# TC_IC3.net
KiCad netlist of a schematic drawn in Altium Designer
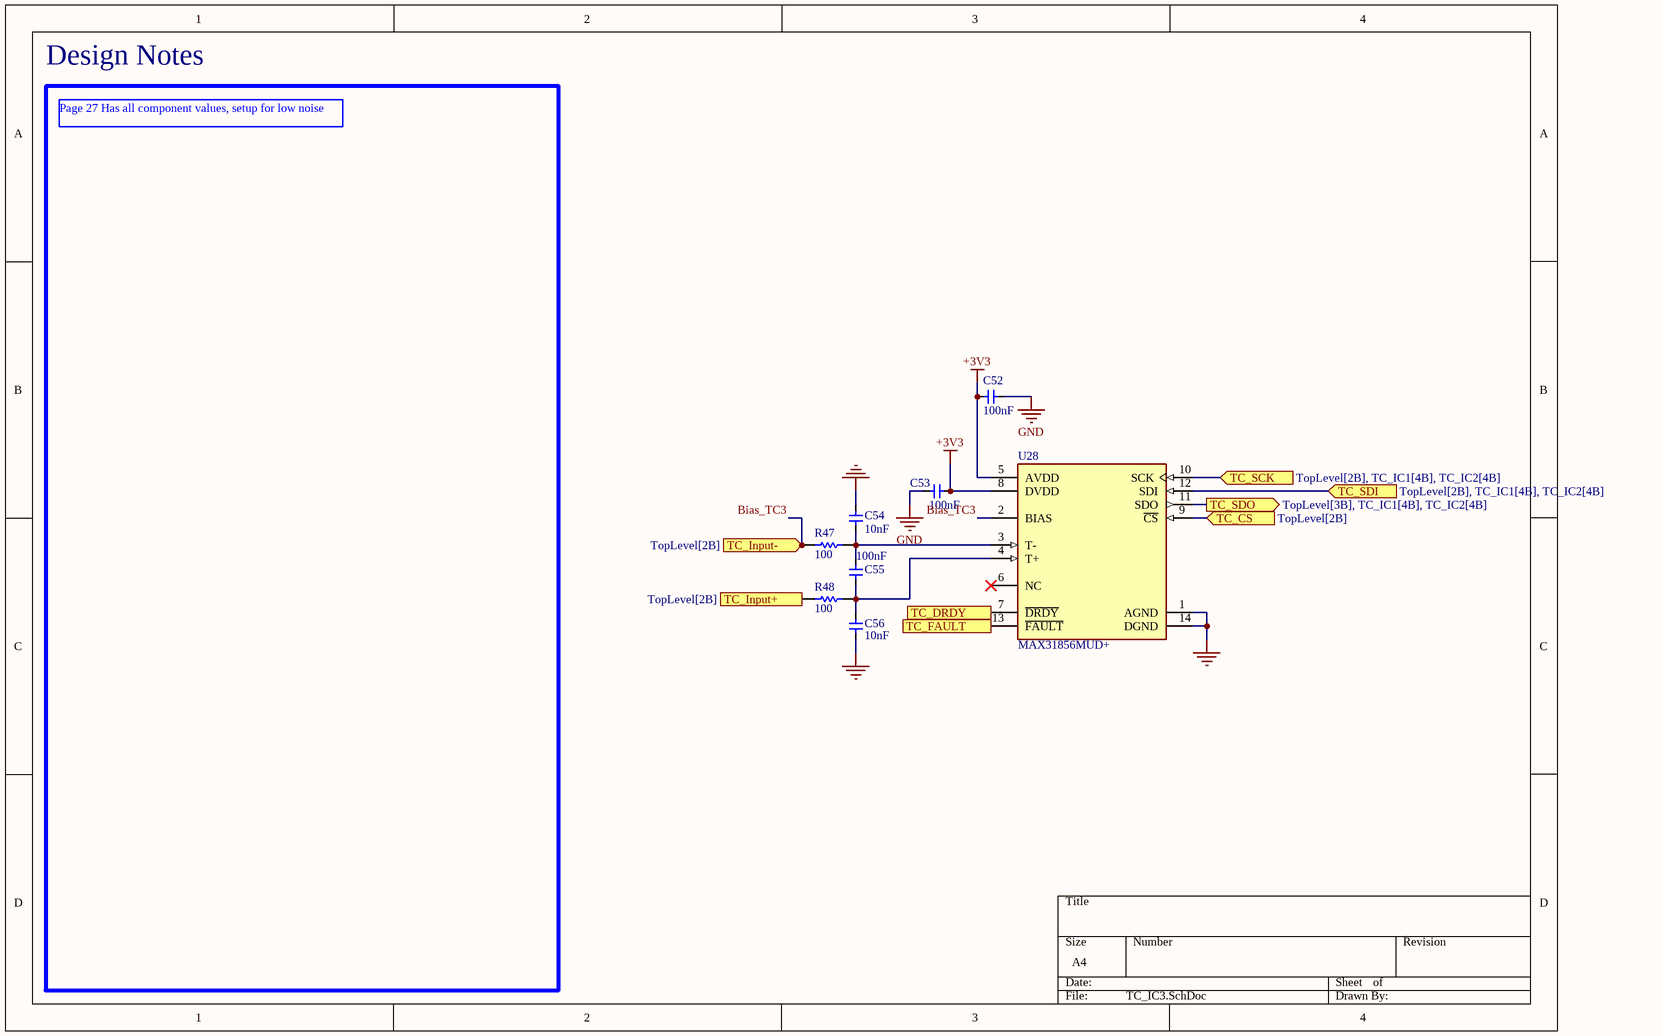
[diagram p0: TC_IC3.SchDoc]

(export (version "E")
  (design (tool "Eeschema 10.0.6"))
  (components
    (comp (ref "C52")
      (value "100nF")
      (footprint "0.1uF-FP-CGA3E-0_3-0_1-IPC_A")
      (description "CGA3E2X7R1E104K080AA CAP CER 0.1UF 25V X7R 0603")
      (fields
        (field (name "TOLERANCE") "10%")
        (field (name "MANUFACTURER") "TDK Corporation")
        (field (name "SOURCE") "PlumBay_SchLib.SchLib")
      )
      (libsource (lib "University of Calgary - SOAR") (part "100nF"))
    )
    (comp (ref "C53")
      (value "100nF")
      (footprint "0.1uF-FP-CGA3E-0_3-0_1-IPC_A")
      (description "CGA3E2X7R1E104K080AA CAP CER 0.1UF 25V X7R 0603")
      (fields
        (field (name "TOLERANCE") "10%")
        (field (name "MANUFACTURER") "TDK Corporation")
        (field (name "SOURCE") "PlumBay_SchLib.SchLib")
      )
      (libsource (lib "University of Calgary - SOAR") (part "100nF"))
    )
    (comp (ref "C54")
      (value "10nF")
      (footprint "10000pF-CAP_1608_TDK")
      (description "CAP CER 10000PF 50V X7R 0603")
      (fields
        (field (name "MANUFACTURER") "TDK Corporation")
        (field (name "TOLERANCE") "10%")
        (field (name "SOURCE") "PlumBay_SchLib.SchLib")
      )
      (libsource (lib "University of Calgary - SOAR") (part "CGA3E2X7R1H103K080AA"))
    )
    (comp (ref "C55")
      (value "100nF")
      (footprint "0.1uF-FP-CGA3E-0_3-0_1-IPC_A")
      (description "CGA3E2X7R1E104K080AA CAP CER 0.1UF 25V X7R 0603")
      (fields
        (field (name "TOLERANCE") "10%")
        (field (name "MANUFACTURER") "TDK Corporation")
        (field (name "SOURCE") "PlumBay_SchLib.SchLib")
      )
      (libsource (lib "University of Calgary - SOAR") (part "100nF"))
    )
    (comp (ref "C56")
      (value "10nF")
      (footprint "10000pF-CAP_1608_TDK")
      (description "CAP CER 10000PF 50V X7R 0603")
      (fields
        (field (name "MANUFACTURER") "TDK Corporation")
        (field (name "TOLERANCE") "10%")
        (field (name "SOURCE") "PlumBay_SchLib.SchLib")
      )
      (libsource (lib "University of Calgary - SOAR") (part "CGA3E2X7R1H103K080AA"))
    )
    (comp (ref "R47")
      (value "100")
      (footprint "RESC1608X55X30LL15T15")
      (fields
        (field (name "POWER") "100mW")
        (field (name "TOLERANCE") "1%")
        (field (name "Comment") "ERJ-3EKF1000V")
      )
      (libsource (lib "University of Calgary - SOAR") (part "RES"))
    )
    (comp (ref "R48")
      (value "100")
      (footprint "RESC1608X55X30LL15T15")
      (fields
        (field (name "POWER") "100mW")
        (field (name "TOLERANCE") "1%")
        (field (name "Comment") "ERJ-3EKF1000V")
      )
      (libsource (lib "University of Calgary - SOAR") (part "RES"))
    )
    (comp (ref "U28")
      (value "MAX31856MUD+")
      (footprint "FP-U14-2-MFG")
      (description "Analog Circuit, 1 Func, PDSO14")
      (libsource (lib "University of Calgary - SOAR") (part "746ee3d58a922cadd982a8de1b076a0"))
    )
  )
  (nets
    (net (code "1") (name "+3V3") (class "Default")
      (node (ref "C52") (pin "1") (pinfunction "1_1") (pintype "passive"))
      (node (ref "C53") (pin "1") (pinfunction "1_1") (pintype "passive"))
      (node (ref "U28") (pin "5") (pinfunction "AVDD_5") (pintype "power_in"))
      (node (ref "U28") (pin "8") (pinfunction "DVDD_8") (pintype "power_in"))
    )
    (net (code "2") (name "/Bias_TC3") (class "Default")
      (node (ref "R47") (pin "2") (pinfunction "2_2") (pintype "passive"))
      (node (ref "U28") (pin "2") (pinfunction "BIAS_2") (pintype "passive"))
    )
    (net (code "3") (name "/TC_CS") (class "Default")
      (node (ref "U28") (pin "9") (pinfunction "~{CS}_9") (pintype "input"))
    )
    (net (code "4") (name "/TC_DRDY") (class "Default")
      (node (ref "U28") (pin "7") (pinfunction "~{DRDY}_7") (pintype "passive"))
    )
    (net (code "5") (name "/TC_FAULT") (class "Default")
      (node (ref "U28") (pin "13") (pinfunction "~{FAULT}_13") (pintype "passive"))
    )
    (net (code "6") (name "/TC_Input+") (class "Default")
      (node (ref "R48") (pin "2") (pinfunction "2_2") (pintype "passive"))
    )
    (net (code "7") (name "/TC_SCK") (class "Default")
      (node (ref "U28") (pin "10") (pinfunction "SCK_10") (pintype "input"))
    )
    (net (code "8") (name "/TC_SDI") (class "Default")
      (node (ref "U28") (pin "12") (pinfunction "SDI_12") (pintype "input"))
    )
    (net (code "9") (name "/TC_SDO") (class "Default")
      (node (ref "U28") (pin "11") (pinfunction "SDO_11") (pintype "output"))
    )
    (net (code "10") (name "GND") (class "Default")
      (node (ref "C52") (pin "2") (pinfunction "2_2") (pintype "passive"))
      (node (ref "C53") (pin "2") (pinfunction "2_2") (pintype "passive"))
      (node (ref "C54") (pin "1") (pinfunction "1_1") (pintype "passive"))
      (node (ref "C56") (pin "1") (pinfunction "1_1") (pintype "passive"))
      (node (ref "U28") (pin "1") (pinfunction "AGND_1") (pintype "power_in"))
      (node (ref "U28") (pin "14") (pinfunction "DGND_14") (pintype "power_in"))
    )
    (net (code "11") (name "Net-(U28-T+)") (class "Default")
      (node (ref "C55") (pin "1") (pinfunction "1_1") (pintype "passive"))
      (node (ref "C56") (pin "2") (pinfunction "2_2") (pintype "passive"))
      (node (ref "R48") (pin "1") (pinfunction "1_1") (pintype "passive"))
      (node (ref "U28") (pin "4") (pinfunction "T+_4") (pintype "input"))
    )
    (net (code "12") (name "Net-(U28-T-)") (class "Default")
      (node (ref "C54") (pin "2") (pinfunction "2_2") (pintype "passive"))
      (node (ref "C55") (pin "2") (pinfunction "2_2") (pintype "passive"))
      (node (ref "R47") (pin "1") (pinfunction "1_1") (pintype "passive"))
      (node (ref "U28") (pin "3") (pinfunction "T-_3") (pintype "input"))
    )
    (net (code "13") (name "unconnected-(U28-NC-Pad6)") (class "Default")
      (node (ref "U28") (pin "6") (pinfunction "NC_6") (pintype "passive+no_connect"))
    )
  )
)
